# RE01.net
KiCad netlist of a schematic drawn in EAGLE
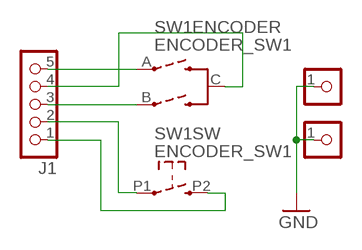
[diagram p0: schematic, sheet 1]

(export (version "E")
  (design (tool "Eeschema 10.0.6"))
  (components
    (comp (ref "H1")
      (value "PROTO_VIAS_01X01")
      (footprint "eagle-import:PROTO_VIAS_01X01")
      (libsource (lib "eagle-import") (part "PROTO_VIAS_01X01"))
    )
    (comp (ref "H2")
      (value "PROTO_VIAS_01X01")
      (footprint "eagle-import:PROTO_VIAS_01X01")
      (libsource (lib "eagle-import") (part "PROTO_VIAS_01X01"))
    )
    (comp (ref "J1")
      (value "CON_HEADER_1X05-PTH")
      (footprint "eagle-import:M1X5")
      (libsource (lib "eagle-import") (part "CON_HEADER_1X05-PTH"))
    )
    (comp (ref "SW1")
      (value "ENCODER_SW1")
      (footprint "eagle-import:GENERIC_12MM_INCREMENTAL_ENCODER")
      (libsource (lib "eagle-import") (part "ENCODER_SW1"))
    )
  )
  (nets
    (net (code "1") (name "GND") (class "Default")
      (node (ref "H1") (pin "1") (pinfunction "1_1") (pintype "passive"))
      (node (ref "H2") (pin "1") (pinfunction "1_1") (pintype "passive"))
    )
    (net (code "2") (name "Net-(J1-Pad3)") (class "Default")
      (node (ref "J1") (pin "3") (pinfunction "3_3") (pintype "bidirectional"))
      (node (ref "SW1") (pin "B") (pinfunction "B_B") (pintype "passive"))
    )
    (net (code "3") (name "Net-(J1-Pad4)") (class "Default")
      (node (ref "J1") (pin "4") (pinfunction "4_4") (pintype "bidirectional"))
      (node (ref "SW1") (pin "C") (pinfunction "C_C") (pintype "passive"))
    )
    (net (code "4") (name "Net-(J1-Pad5)") (class "Default")
      (node (ref "J1") (pin "5") (pinfunction "5_5") (pintype "bidirectional"))
      (node (ref "SW1") (pin "A") (pinfunction "A_A") (pintype "passive"))
    )
    (net (code "5") (name "Net-(SW1B-1)") (class "Default")
      (node (ref "J1") (pin "2") (pinfunction "2_2") (pintype "bidirectional"))
      (node (ref "SW1") (pin "P1") (pinfunction "1_P1") (pintype "passive"))
    )
    (net (code "6") (name "Net-(SW1B-2)") (class "Default")
      (node (ref "J1") (pin "1") (pinfunction "1_1") (pintype "bidirectional"))
      (node (ref "SW1") (pin "P2") (pinfunction "2_P2") (pintype "passive"))
    )
  )
)
